# wirelessnode.net
KiCad netlist of a schematic drawn in EAGLE
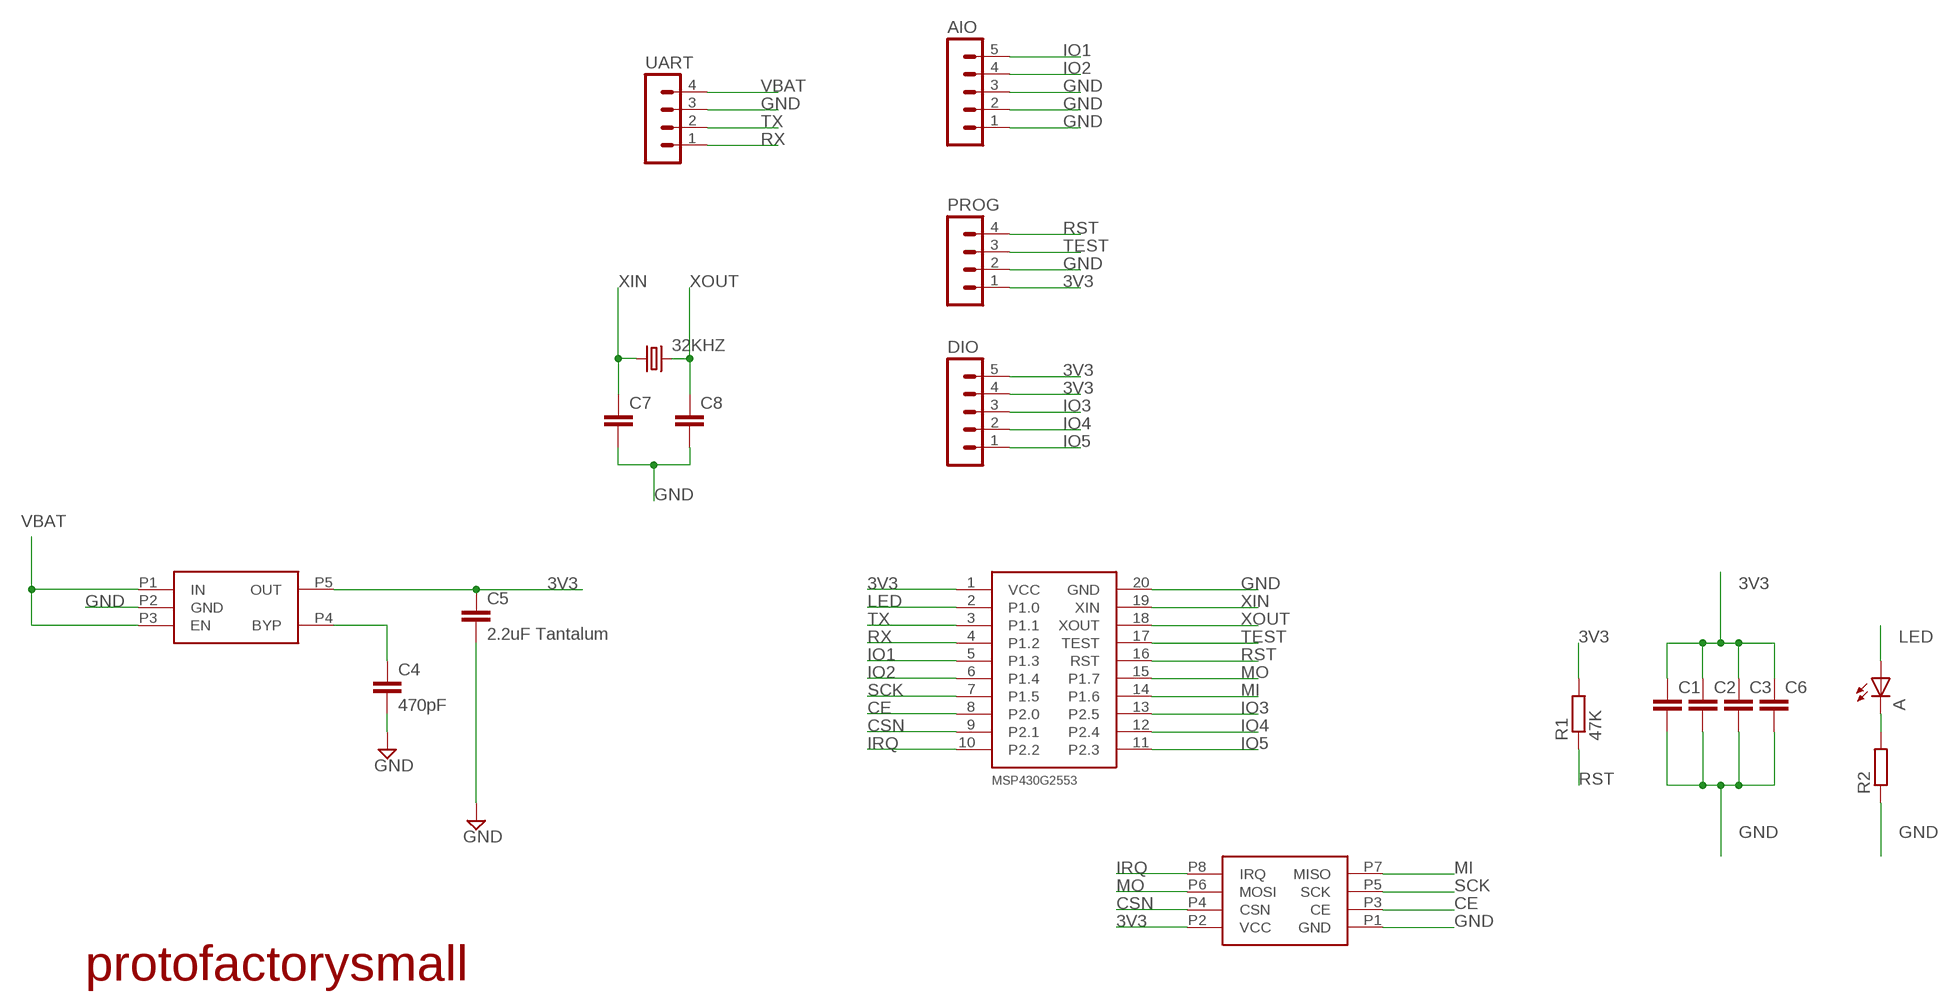
[diagram p0: schematic, sheet 1]

(export (version "E")
  (design (tool "Eeschema 10.0.6"))
  (components
    (comp (ref "32KHZ")
      (value "CRYSTALTC26H")
      (footprint "eagle-import:TC26H")
      (libsource (lib "eagle-import") (part "CRYSTALTC26H"))
    )
    (comp (ref "A")
      (value "LEDSML0603")
      (footprint "eagle-import:SML0603")
      (libsource (lib "eagle-import") (part "LEDSML0603"))
    )
    (comp (ref "AIO")
      (value "MA05-1")
      (footprint "eagle-import:MA05-1")
      (libsource (lib "eagle-import") (part "MA05-1"))
    )
    (comp (ref "C1")
      (value "C-EUC0603")
      (footprint "eagle-import:C0603")
      (libsource (lib "eagle-import") (part "C-EUC0603"))
    )
    (comp (ref "C2")
      (value "C-EUC0603")
      (footprint "eagle-import:C0603")
      (libsource (lib "eagle-import") (part "C-EUC0603"))
    )
    (comp (ref "C3")
      (value "C-EUC0603")
      (footprint "eagle-import:C0603")
      (libsource (lib "eagle-import") (part "C-EUC0603"))
    )
    (comp (ref "C4")
      (value "470pF")
      (footprint "eagle-import:C0603")
      (libsource (lib "eagle-import") (part "C-EUC0603"))
    )
    (comp (ref "C5")
      (value "2.2uF Tantalum")
      (footprint "eagle-import:C3225")
      (libsource (lib "eagle-import") (part "C-EUC3225"))
    )
    (comp (ref "C6")
      (value "C-EUC0603")
      (footprint "eagle-import:C0603")
      (libsource (lib "eagle-import") (part "C-EUC0603"))
    )
    (comp (ref "C7")
      (value "C-EUC0603")
      (footprint "eagle-import:C0603")
      (libsource (lib "eagle-import") (part "C-EUC0603"))
    )
    (comp (ref "C8")
      (value "C-EUC0603")
      (footprint "eagle-import:C0603")
      (libsource (lib "eagle-import") (part "C-EUC0603"))
    )
    (comp (ref "DIO")
      (value "MA05-1")
      (footprint "eagle-import:MA05-1")
      (libsource (lib "eagle-import") (part "MA05-1"))
    )
    (comp (ref "MSP430G2553")
      (value "MSP430G2553_20PINMSP430G2553")
      (footprint "eagle-import:DIL20")
      (libsource (lib "eagle-import") (part "MSP430G2553_20PINMSP430G2553"))
    )
    (comp (ref "PROG")
      (value "MA04-1")
      (footprint "eagle-import:MA04-1")
      (libsource (lib "eagle-import") (part "MA04-1"))
    )
    (comp (ref "R1")
      (value "47K")
      (footprint "eagle-import:R0603")
      (libsource (lib "eagle-import") (part "R-EU_R0603"))
    )
    (comp (ref "R2")
      (value "R-EU_R0603")
      (footprint "eagle-import:R0603")
      (libsource (lib "eagle-import") (part "R-EU_R0603"))
    )
    (comp (ref "RF")
      (value "NRF24L01NRF24L01")
      (footprint "eagle-import:NRF24L01")
      (libsource (lib "eagle-import") (part "NRF24L01NRF24L01"))
    )
    (comp (ref "U$1")
      (value "SMALLPROTOLOGOLOGO")
      (footprint "eagle-import:LOGO_SMALL")
      (libsource (lib "eagle-import") (part "SMALLPROTOLOGOLOGO"))
    )
    (comp (ref "U$3")
      (value "MIC5219-X.XBM5MIC5219-3.3YM5TR")
      (footprint "eagle-import:SOT-23-5")
      (libsource (lib "eagle-import") (part "MIC5219-X.XBM5MIC5219-3.3YM5TR"))
    )
    (comp (ref "UART")
      (value "MA04-1")
      (footprint "eagle-import:MA04-1")
      (libsource (lib "eagle-import") (part "MA04-1"))
    )
  )
  (nets
    (net (code "1") (name "/3V3") (class "Default")
      (node (ref "C1") (pin "1") (pinfunction "1_1") (pintype "passive"))
      (node (ref "C2") (pin "1") (pinfunction "1_1") (pintype "passive"))
      (node (ref "C3") (pin "1") (pinfunction "1_1") (pintype "passive"))
      (node (ref "C5") (pin "1") (pinfunction "1_1") (pintype "passive"))
      (node (ref "C6") (pin "1") (pinfunction "1_1") (pintype "passive"))
      (node (ref "DIO") (pin "4") (pinfunction "4_4") (pintype "passive"))
      (node (ref "DIO") (pin "5") (pinfunction "5_5") (pintype "passive"))
      (node (ref "MSP430G2553") (pin "1") (pinfunction "VCC_1") (pintype "bidirectional"))
      (node (ref "PROG") (pin "1") (pinfunction "1_1") (pintype "passive"))
      (node (ref "R1") (pin "2") (pinfunction "2_2") (pintype "passive"))
      (node (ref "RF") (pin "P2") (pinfunction "VCC_P2") (pintype "bidirectional"))
      (node (ref "U$3") (pin "P5") (pinfunction "OUT_P5") (pintype "bidirectional"))
    )
    (net (code "2") (name "/CE") (class "Default")
      (node (ref "MSP430G2553") (pin "8") (pinfunction "P2.0_8") (pintype "bidirectional"))
      (node (ref "RF") (pin "P3") (pinfunction "CE_P3") (pintype "bidirectional"))
    )
    (net (code "3") (name "/CSN") (class "Default")
      (node (ref "MSP430G2553") (pin "9") (pinfunction "P2.1_9") (pintype "bidirectional"))
      (node (ref "RF") (pin "P4") (pinfunction "CSN_P4") (pintype "bidirectional"))
    )
    (net (code "4") (name "/IO1") (class "Default")
      (node (ref "AIO") (pin "5") (pinfunction "5_5") (pintype "passive"))
      (node (ref "MSP430G2553") (pin "5") (pinfunction "P1.3_5") (pintype "bidirectional"))
    )
    (net (code "5") (name "/IO2") (class "Default")
      (node (ref "AIO") (pin "4") (pinfunction "4_4") (pintype "passive"))
      (node (ref "MSP430G2553") (pin "6") (pinfunction "P1.4_6") (pintype "bidirectional"))
    )
    (net (code "6") (name "/IO3") (class "Default")
      (node (ref "DIO") (pin "3") (pinfunction "3_3") (pintype "passive"))
      (node (ref "MSP430G2553") (pin "13") (pinfunction "P2.5_13") (pintype "bidirectional"))
    )
    (net (code "7") (name "/IO4") (class "Default")
      (node (ref "DIO") (pin "2") (pinfunction "2_2") (pintype "passive"))
      (node (ref "MSP430G2553") (pin "12") (pinfunction "P2.4_12") (pintype "bidirectional"))
    )
    (net (code "8") (name "/IO5") (class "Default")
      (node (ref "DIO") (pin "1") (pinfunction "1_1") (pintype "passive"))
      (node (ref "MSP430G2553") (pin "11") (pinfunction "P2.3_11") (pintype "bidirectional"))
    )
    (net (code "9") (name "/IRQ") (class "Default")
      (node (ref "MSP430G2553") (pin "10") (pinfunction "P2.2_10") (pintype "bidirectional"))
      (node (ref "RF") (pin "P8") (pinfunction "IRQ_P8") (pintype "bidirectional"))
    )
    (net (code "10") (name "/LED") (class "Default")
      (node (ref "A") (pin "A") (pinfunction "A_A") (pintype "passive"))
      (node (ref "MSP430G2553") (pin "2") (pinfunction "P1.0_2") (pintype "bidirectional"))
    )
    (net (code "11") (name "/MI") (class "Default")
      (node (ref "MSP430G2553") (pin "14") (pinfunction "P1.6_14") (pintype "bidirectional"))
      (node (ref "RF") (pin "P7") (pinfunction "MISO_P7") (pintype "bidirectional"))
    )
    (net (code "12") (name "/MO") (class "Default")
      (node (ref "MSP430G2553") (pin "15") (pinfunction "P1.7_15") (pintype "bidirectional"))
      (node (ref "RF") (pin "P6") (pinfunction "MOSI_P6") (pintype "bidirectional"))
    )
    (net (code "13") (name "/RST") (class "Default")
      (node (ref "MSP430G2553") (pin "16") (pinfunction "RST_16") (pintype "bidirectional"))
      (node (ref "PROG") (pin "4") (pinfunction "4_4") (pintype "passive"))
      (node (ref "R1") (pin "1") (pinfunction "1_1") (pintype "passive"))
    )
    (net (code "14") (name "/RX") (class "Default")
      (node (ref "MSP430G2553") (pin "4") (pinfunction "P1.2_4") (pintype "bidirectional"))
      (node (ref "UART") (pin "1") (pinfunction "1_1") (pintype "passive"))
    )
    (net (code "15") (name "/SCK") (class "Default")
      (node (ref "MSP430G2553") (pin "7") (pinfunction "P1.5_7") (pintype "bidirectional"))
      (node (ref "RF") (pin "P5") (pinfunction "SCK_P5") (pintype "bidirectional"))
    )
    (net (code "16") (name "/TEST") (class "Default")
      (node (ref "MSP430G2553") (pin "17") (pinfunction "TEST_17") (pintype "bidirectional"))
      (node (ref "PROG") (pin "3") (pinfunction "3_3") (pintype "passive"))
    )
    (net (code "17") (name "/TX") (class "Default")
      (node (ref "MSP430G2553") (pin "3") (pinfunction "P1.1_3") (pintype "bidirectional"))
      (node (ref "UART") (pin "2") (pinfunction "2_2") (pintype "passive"))
    )
    (net (code "18") (name "/VBAT") (class "Default")
      (node (ref "U$3") (pin "P1") (pinfunction "IN_P1") (pintype "bidirectional"))
      (node (ref "U$3") (pin "P3") (pinfunction "EN_P3") (pintype "bidirectional"))
      (node (ref "UART") (pin "4") (pinfunction "4_4") (pintype "passive"))
    )
    (net (code "19") (name "/XIN") (class "Default")
      (node (ref "32KHZ") (pin "1") (pinfunction "1_1") (pintype "passive"))
      (node (ref "C7") (pin "1") (pinfunction "1_1") (pintype "passive"))
      (node (ref "MSP430G2553") (pin "19") (pinfunction "XIN_19") (pintype "bidirectional"))
    )
    (net (code "20") (name "/XOUT") (class "Default")
      (node (ref "32KHZ") (pin "2") (pinfunction "2_2") (pintype "passive"))
      (node (ref "C8") (pin "1") (pinfunction "1_1") (pintype "passive"))
      (node (ref "MSP430G2553") (pin "18") (pinfunction "XOUT_18") (pintype "bidirectional"))
    )
    (net (code "21") (name "GND") (class "Default")
      (node (ref "AIO") (pin "1") (pinfunction "1_1") (pintype "passive"))
      (node (ref "AIO") (pin "2") (pinfunction "2_2") (pintype "passive"))
      (node (ref "AIO") (pin "3") (pinfunction "3_3") (pintype "passive"))
      (node (ref "C1") (pin "2") (pinfunction "2_2") (pintype "passive"))
      (node (ref "C2") (pin "2") (pinfunction "2_2") (pintype "passive"))
      (node (ref "C3") (pin "2") (pinfunction "2_2") (pintype "passive"))
      (node (ref "C4") (pin "2") (pinfunction "2_2") (pintype "passive"))
      (node (ref "C5") (pin "2") (pinfunction "2_2") (pintype "passive"))
      (node (ref "C6") (pin "2") (pinfunction "2_2") (pintype "passive"))
      (node (ref "C7") (pin "2") (pinfunction "2_2") (pintype "passive"))
      (node (ref "C8") (pin "2") (pinfunction "2_2") (pintype "passive"))
      (node (ref "MSP430G2553") (pin "20") (pinfunction "GND_20") (pintype "bidirectional"))
      (node (ref "PROG") (pin "2") (pinfunction "2_2") (pintype "passive"))
      (node (ref "R2") (pin "1") (pinfunction "1_1") (pintype "passive"))
      (node (ref "RF") (pin "P1") (pinfunction "GND_P1") (pintype "bidirectional"))
      (node (ref "U$3") (pin "P2") (pinfunction "GND_P2") (pintype "bidirectional"))
      (node (ref "UART") (pin "3") (pinfunction "3_3") (pintype "passive"))
    )
    (net (code "22") (name "Net-(A-PadC)") (class "Default")
      (node (ref "A") (pin "C") (pinfunction "C_C") (pintype "passive"))
      (node (ref "R2") (pin "2") (pinfunction "2_2") (pintype "passive"))
    )
    (net (code "23") (name "Net-(U$3-BYP)") (class "Default")
      (node (ref "C4") (pin "1") (pinfunction "1_1") (pintype "passive"))
      (node (ref "U$3") (pin "P4") (pinfunction "BYP_P4") (pintype "bidirectional"))
    )
  )
)
